# v0_9.net
KiCad netlist of a schematic drawn in EAGLE
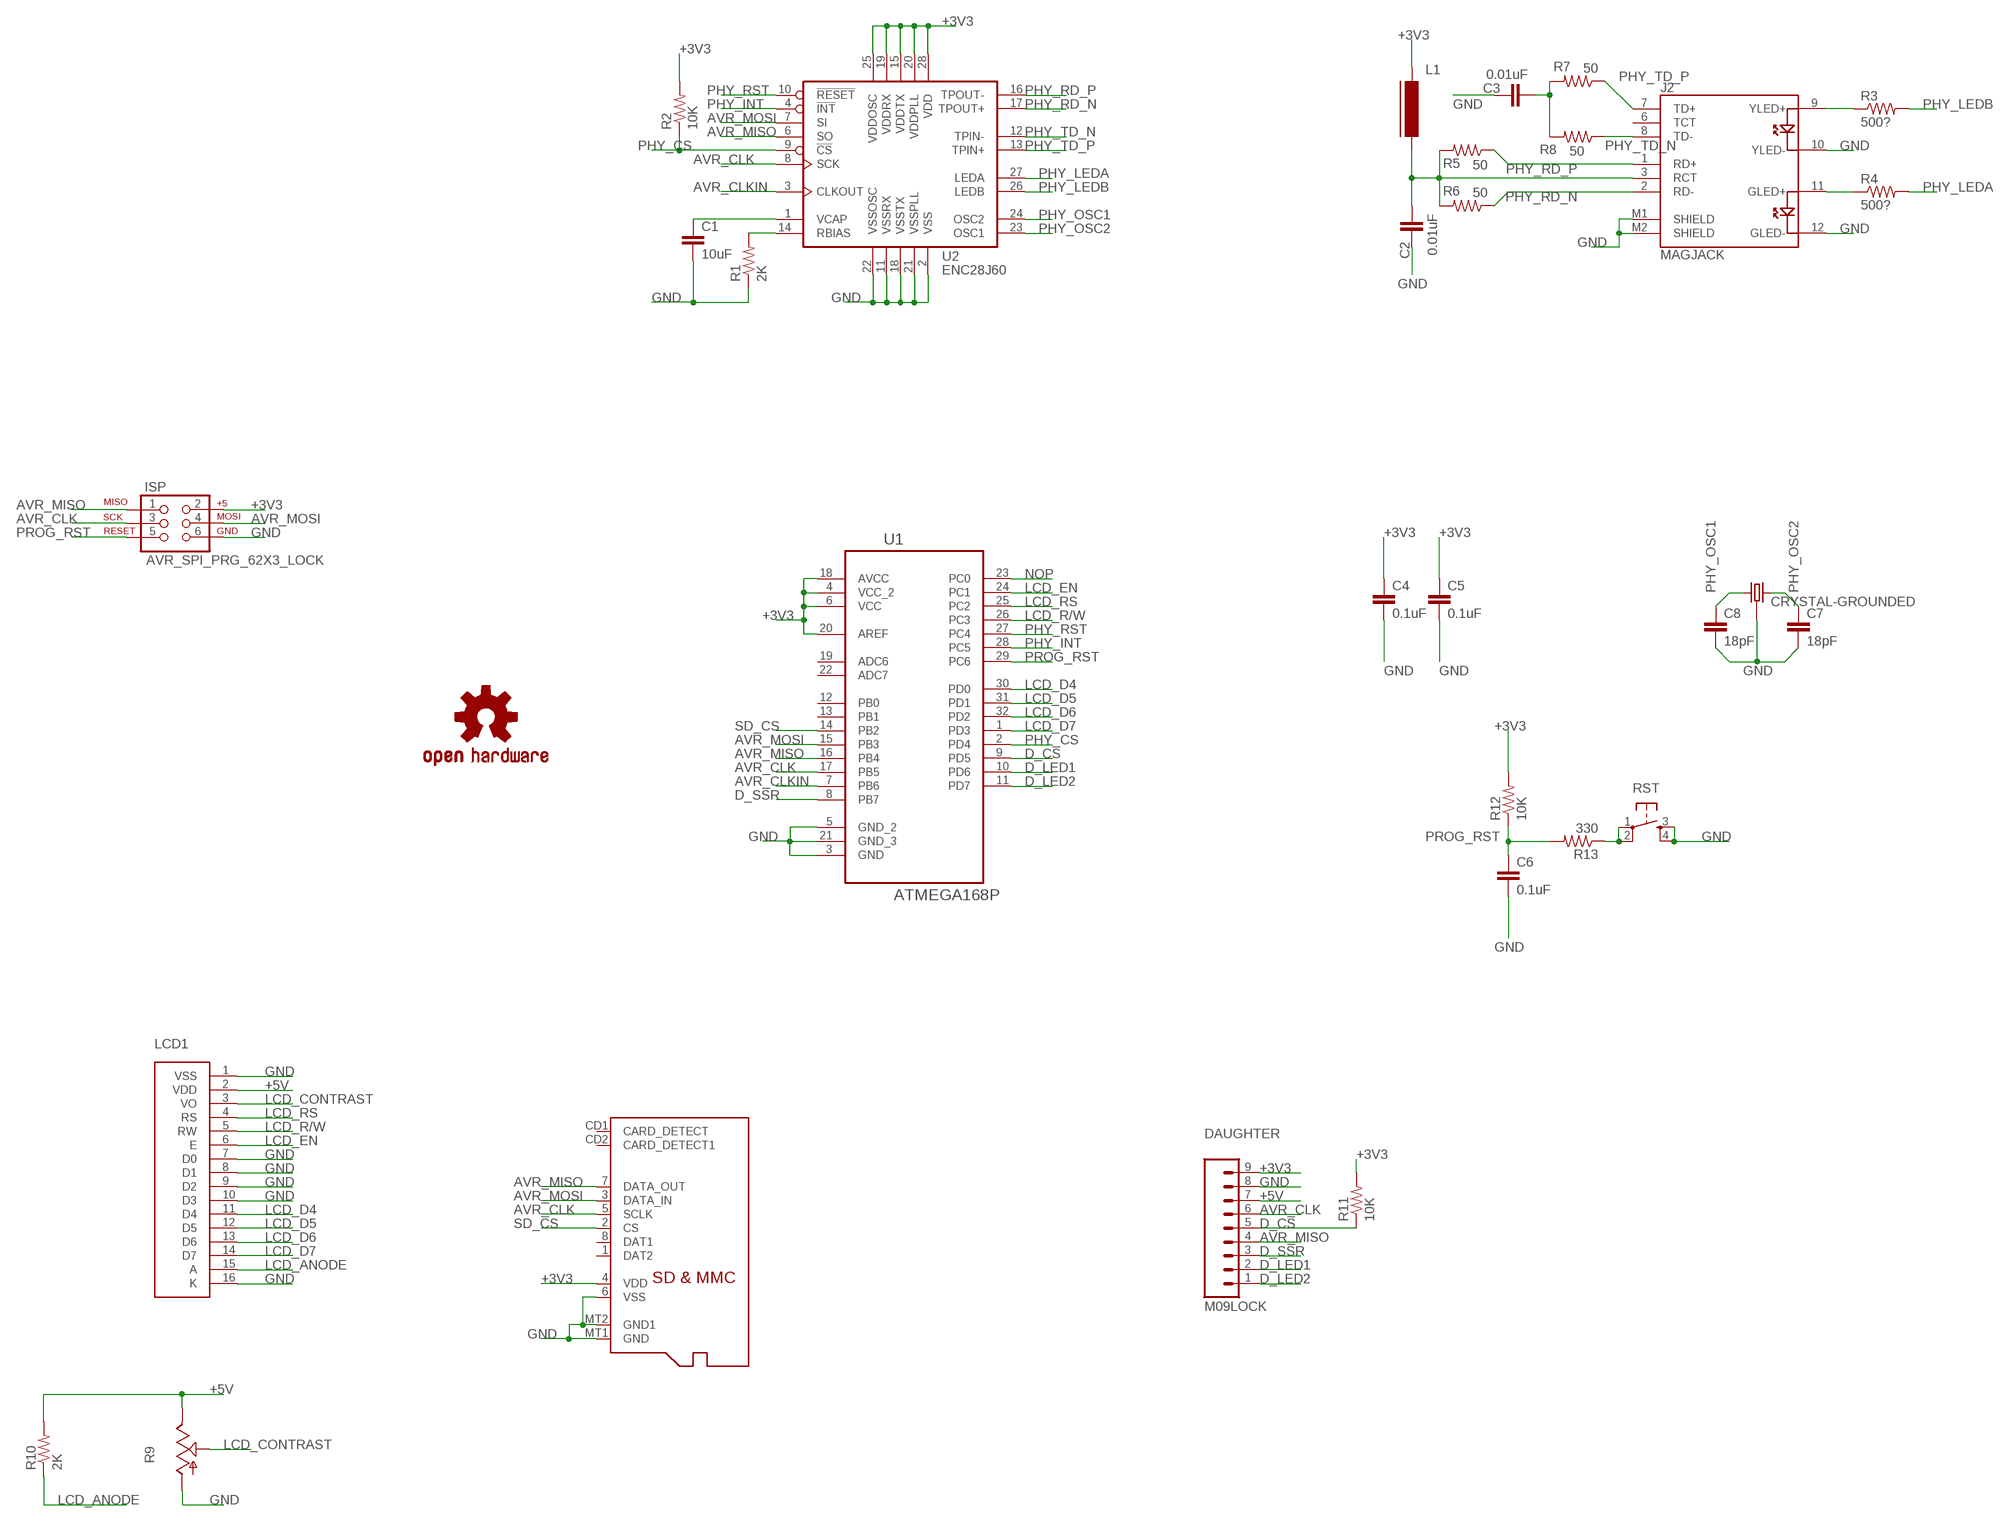
[diagram p0: schematic, sheet 1]

(export (version "E")
  (design (tool "Eeschema 10.0.6"))
  (components
    (comp (ref "C1")
      (value "10uF")
      (footprint "eagle-import:0603-CAP")
      (libsource (lib "eagle-import") (part "10UF-6.3V-20%(0603)"))
    )
    (comp (ref "C2")
      (value "0.01uF")
      (footprint "eagle-import:0603-CAP")
      (libsource (lib "eagle-import") (part "CAP0603-CAP"))
    )
    (comp (ref "C3")
      (value "0.01uF")
      (footprint "eagle-import:0603-CAP")
      (libsource (lib "eagle-import") (part "CAP0603-CAP"))
    )
    (comp (ref "C4")
      (value "0.1uF")
      (footprint "eagle-import:0402-CAP")
      (libsource (lib "eagle-import") (part "CAP0402-CAP"))
    )
    (comp (ref "C5")
      (value "0.1uF")
      (footprint "eagle-import:0402-CAP")
      (libsource (lib "eagle-import") (part "CAP0402-CAP"))
    )
    (comp (ref "C6")
      (value "0.1uF")
      (footprint "eagle-import:0603-CAP")
      (libsource (lib "eagle-import") (part "CAP0603-CAP"))
    )
    (comp (ref "C7")
      (value "18pF")
      (footprint "eagle-import:0402-CAP")
      (libsource (lib "eagle-import") (part "CAP0402-CAP"))
    )
    (comp (ref "C8")
      (value "18pF")
      (footprint "eagle-import:0402-CAP")
      (libsource (lib "eagle-import") (part "CAP0402-CAP"))
    )
    (comp (ref "DAUGHTER")
      (value "M09LOCK")
      (footprint "eagle-import:1X09_LOCK")
      (libsource (lib "eagle-import") (part "M09LOCK"))
    )
    (comp (ref "ISP")
      (value "AVR_SPI_PRG_62X3_LOCK")
      (footprint "eagle-import:2X3_LOCK")
      (libsource (lib "eagle-import") (part "AVR_SPI_PRG_62X3_LOCK"))
    )
    (comp (ref "J2")
      (value "MAGJACK")
      (footprint "eagle-import:MAGJACK")
      (libsource (lib "eagle-import") (part "MAGJACK"))
    )
    (comp (ref "L1")
      (value "FERRITE-0603")
      (footprint "eagle-import:FB603")
      (libsource (lib "eagle-import") (part "FERRITE-0603"))
    )
    (comp (ref "LCD1")
      (value "HD44780")
      (footprint "eagle-import:.1_16PIN")
      (libsource (lib "eagle-import") (part "HD44780"))
    )
    (comp (ref "LOGO1")
      (value "OSHW-LOGOS")
      (footprint "eagle-import:OSHW-LOGO-S")
      (libsource (lib "eagle-import") (part "OSHW-LOGOS"))
    )
    (comp (ref "R1")
      (value "2K")
      (footprint "eagle-import:0603-RES")
      (libsource (lib "eagle-import") (part "RESISTOR0603-RES"))
    )
    (comp (ref "R2")
      (value "10K")
      (footprint "eagle-import:0603-RES")
      (libsource (lib "eagle-import") (part "RESISTOR0603-RES"))
    )
    (comp (ref "R3")
      (value "500?")
      (footprint "eagle-import:0603-RES")
      (libsource (lib "eagle-import") (part "RESISTOR0603-RES"))
    )
    (comp (ref "R4")
      (value "500?")
      (footprint "eagle-import:0603-RES")
      (libsource (lib "eagle-import") (part "RESISTOR0603-RES"))
    )
    (comp (ref "R5")
      (value "50")
      (footprint "eagle-import:0603-RES")
      (libsource (lib "eagle-import") (part "RESISTOR0603-RES"))
    )
    (comp (ref "R6")
      (value "50")
      (footprint "eagle-import:0603-RES")
      (libsource (lib "eagle-import") (part "RESISTOR0603-RES"))
    )
    (comp (ref "R7")
      (value "50")
      (footprint "eagle-import:0603-RES")
      (libsource (lib "eagle-import") (part "RESISTOR0603-RES"))
    )
    (comp (ref "R8")
      (value "50")
      (footprint "eagle-import:0603-RES")
      (libsource (lib "eagle-import") (part "RESISTOR0603-RES"))
    )
    (comp (ref "R9")
      (value "TRIM_US-B64Y")
      (footprint "eagle-import:B64Y")
      (libsource (lib "eagle-import") (part "TRIM_US-B64Y"))
    )
    (comp (ref "R10")
      (value "2K")
      (footprint "eagle-import:0603-RES")
      (libsource (lib "eagle-import") (part "RESISTOR0603-RES"))
    )
    (comp (ref "R11")
      (value "10K")
      (footprint "eagle-import:0603-RES")
      (libsource (lib "eagle-import") (part "RESISTOR0603-RES"))
    )
    (comp (ref "R12")
      (value "10K")
      (footprint "eagle-import:0603-RES")
      (libsource (lib "eagle-import") (part "RESISTOR0603-RES"))
    )
    (comp (ref "R13")
      (value "330")
      (footprint "eagle-import:0603-RES")
      (libsource (lib "eagle-import") (part "RESISTOR0603-RES"))
    )
    (comp (ref "RST")
      (value "TAC_SWITCHSMD")
      (footprint "eagle-import:TACTILE-SWITCH-SMD")
      (libsource (lib "eagle-import") (part "TAC_SWITCHSMD"))
    )
    (comp (ref "SD")
      (value "MICROSD")
      (footprint "eagle-import:MICROSD")
      (libsource (lib "eagle-import") (part "MICROSD"))
    )
    (comp (ref "U1")
      (value "ATMEGA168P")
      (footprint "eagle-import:QFP80P900X900X120-32N")
      (fields (field (name "MPN") "ATMEGA168P-20AU"))
      (libsource (lib "eagle-import") (part "ATMEGA168P-20AU"))
    )
    (comp (ref "U2")
      (value "ENC28J60")
      (footprint "eagle-import:SOIC-28W")
      (libsource (lib "eagle-import") (part "IC_ENC28J60-SOIC-28"))
    )
    (comp (ref "Y1")
      (value "CRYSTAL-GROUNDED")
      (footprint "eagle-import:CRYSTAL-SMD-5X3")
      (libsource (lib "eagle-import") (part "CRYSTAL-GROUNDED"))
    )
  )
  (nets
    (net (code "1") (name "/+3V3") (class "Default")
      (node (ref "C4") (pin "1") (pinfunction "1_1") (pintype "passive"))
      (node (ref "C5") (pin "1") (pinfunction "1_1") (pintype "passive"))
      (node (ref "DAUGHTER") (pin "9") (pinfunction "9_9") (pintype "passive"))
      (node (ref "ISP") (pin "2") (pinfunction "2_2") (pintype "passive"))
      (node (ref "L1") (pin "1") (pinfunction "1_1") (pintype "passive"))
      (node (ref "R11") (pin "2") (pinfunction "2_2") (pintype "passive"))
      (node (ref "R12") (pin "2") (pinfunction "2_2") (pintype "passive"))
      (node (ref "R2") (pin "2") (pinfunction "2_2") (pintype "passive"))
      (node (ref "SD") (pin "4") (pinfunction "VDD_4") (pintype "power_in"))
      (node (ref "U1") (pin "18") (pinfunction "AVCC_18") (pintype "power_in"))
      (node (ref "U1") (pin "20") (pinfunction "AREF_20") (pintype "input"))
      (node (ref "U1") (pin "4") (pinfunction "VCC_2_4") (pintype "power_in"))
      (node (ref "U1") (pin "6") (pinfunction "VCC_6") (pintype "power_in"))
      (node (ref "U2") (pin "15") (pinfunction "VDDTX_15") (pintype "power_in"))
      (node (ref "U2") (pin "19") (pinfunction "VDDRX_19") (pintype "power_in"))
      (node (ref "U2") (pin "20") (pinfunction "VDDPLL_20") (pintype "power_in"))
      (node (ref "U2") (pin "25") (pinfunction "VDDOSC_25") (pintype "power_in"))
      (node (ref "U2") (pin "28") (pinfunction "VDD_28") (pintype "power_in"))
    )
    (net (code "2") (name "/+5V") (class "Default")
      (node (ref "DAUGHTER") (pin "7") (pinfunction "7_7") (pintype "passive"))
      (node (ref "LCD1") (pin "2") (pinfunction "VDD_2") (pintype "bidirectional"))
      (node (ref "R10") (pin "2") (pinfunction "2_2") (pintype "passive"))
      (node (ref "R9") (pin "E") (pinfunction "E_E") (pintype "passive"))
    )
    (net (code "3") (name "/AVR_CLK") (class "Default")
      (node (ref "DAUGHTER") (pin "6") (pinfunction "6_6") (pintype "passive"))
      (node (ref "ISP") (pin "3") (pinfunction "3_3") (pintype "passive"))
      (node (ref "SD") (pin "5") (pinfunction "SCLK_5") (pintype "input"))
      (node (ref "U1") (pin "17") (pinfunction "PB5_17") (pintype "bidirectional"))
      (node (ref "U2") (pin "8") (pinfunction "SCK_8") (pintype "input"))
    )
    (net (code "4") (name "/AVR_CLKIN") (class "Default")
      (node (ref "U1") (pin "7") (pinfunction "PB6_7") (pintype "bidirectional"))
      (node (ref "U2") (pin "3") (pinfunction "CLKOUT_3") (pintype "output"))
    )
    (net (code "5") (name "/AVR_MISO") (class "Default")
      (node (ref "DAUGHTER") (pin "4") (pinfunction "4_4") (pintype "passive"))
      (node (ref "ISP") (pin "1") (pinfunction "1_1") (pintype "passive"))
      (node (ref "SD") (pin "7") (pinfunction "DATA_OUT_7") (pintype "output"))
      (node (ref "U1") (pin "16") (pinfunction "PB4_16") (pintype "bidirectional"))
      (node (ref "U2") (pin "6") (pinfunction "SO_6") (pintype "output"))
    )
    (net (code "6") (name "/AVR_MOSI") (class "Default")
      (node (ref "ISP") (pin "4") (pinfunction "4_4") (pintype "passive"))
      (node (ref "SD") (pin "3") (pinfunction "DATA_IN_3") (pintype "input"))
      (node (ref "U1") (pin "15") (pinfunction "PB3_15") (pintype "bidirectional"))
      (node (ref "U2") (pin "7") (pinfunction "SI_7") (pintype "input"))
    )
    (net (code "7") (name "/D_CS") (class "Default")
      (node (ref "DAUGHTER") (pin "5") (pinfunction "5_5") (pintype "passive"))
      (node (ref "R11") (pin "1") (pinfunction "1_1") (pintype "passive"))
      (node (ref "U1") (pin "9") (pinfunction "PD5_9") (pintype "bidirectional"))
    )
    (net (code "8") (name "/D_LED1") (class "Default")
      (node (ref "DAUGHTER") (pin "2") (pinfunction "2_2") (pintype "passive"))
      (node (ref "U1") (pin "10") (pinfunction "PD6_10") (pintype "bidirectional"))
    )
    (net (code "9") (name "/D_LED2") (class "Default")
      (node (ref "DAUGHTER") (pin "1") (pinfunction "1_1") (pintype "passive"))
      (node (ref "U1") (pin "11") (pinfunction "PD7_11") (pintype "bidirectional"))
    )
    (net (code "10") (name "/D_SSR") (class "Default")
      (node (ref "DAUGHTER") (pin "3") (pinfunction "3_3") (pintype "passive"))
      (node (ref "U1") (pin "8") (pinfunction "PB7_8") (pintype "bidirectional"))
    )
    (net (code "11") (name "/GND") (class "Default")
      (node (ref "C1") (pin "2") (pinfunction "2_2") (pintype "passive"))
      (node (ref "C2") (pin "1") (pinfunction "1_1") (pintype "passive"))
      (node (ref "C3") (pin "1") (pinfunction "1_1") (pintype "passive"))
      (node (ref "C4") (pin "2") (pinfunction "2_2") (pintype "passive"))
      (node (ref "C5") (pin "2") (pinfunction "2_2") (pintype "passive"))
      (node (ref "C6") (pin "2") (pinfunction "2_2") (pintype "passive"))
      (node (ref "C7") (pin "2") (pinfunction "2_2") (pintype "passive"))
      (node (ref "C8") (pin "2") (pinfunction "2_2") (pintype "passive"))
      (node (ref "DAUGHTER") (pin "8") (pinfunction "8_8") (pintype "passive"))
      (node (ref "ISP") (pin "6") (pinfunction "6_6") (pintype "passive"))
      (node (ref "J2") (pin "10") (pinfunction "YLED-_10") (pintype "bidirectional"))
      (node (ref "J2") (pin "12") (pinfunction "GLED-_12") (pintype "bidirectional"))
      (node (ref "J2") (pin "M1") (pinfunction "SHIELD_M1") (pintype "bidirectional"))
      (node (ref "J2") (pin "M2") (pinfunction "SHIELD_M2") (pintype "bidirectional"))
      (node (ref "LCD1") (pin "1") (pinfunction "VSS_1") (pintype "bidirectional"))
      (node (ref "LCD1") (pin "10") (pinfunction "D3_10") (pintype "bidirectional"))
      (node (ref "LCD1") (pin "16") (pinfunction "K_16") (pintype "bidirectional"))
      (node (ref "LCD1") (pin "7") (pinfunction "D0_7") (pintype "bidirectional"))
      (node (ref "LCD1") (pin "8") (pinfunction "D1_8") (pintype "bidirectional"))
      (node (ref "LCD1") (pin "9") (pinfunction "D2_9") (pintype "bidirectional"))
      (node (ref "R1") (pin "1") (pinfunction "1_1") (pintype "passive"))
      (node (ref "R9") (pin "A") (pinfunction "A_A") (pintype "passive"))
      (node (ref "RST") (pin "3") (pinfunction "3_3") (pintype "passive"))
      (node (ref "RST") (pin "4") (pinfunction "4_4") (pintype "passive"))
      (node (ref "SD") (pin "6") (pinfunction "VSS_6") (pintype "power_in"))
      (node (ref "SD") (pin "MT1") (pinfunction "GND_MT1") (pintype "power_in"))
      (node (ref "SD") (pin "MT2") (pinfunction "GND1_MT2") (pintype "power_in"))
      (node (ref "U1") (pin "21") (pinfunction "GND_3_21") (pintype "passive"))
      (node (ref "U1") (pin "3") (pinfunction "GND_3") (pintype "passive"))
      (node (ref "U1") (pin "5") (pinfunction "GND_2_5") (pintype "passive"))
      (node (ref "U2") (pin "11") (pinfunction "VSSRX_11") (pintype "power_in"))
      (node (ref "U2") (pin "18") (pinfunction "VSSTX_18") (pintype "power_in"))
      (node (ref "U2") (pin "2") (pinfunction "VSS_2") (pintype "power_in"))
      (node (ref "U2") (pin "21") (pinfunction "VSSPLL_21") (pintype "power_in"))
      (node (ref "U2") (pin "22") (pinfunction "VSSOSC_22") (pintype "power_in"))
      (node (ref "Y1") (pin "2") (pinfunction "3_2") (pintype "passive"))
      (node (ref "Y1") (pin "4") (pinfunction "3_4") (pintype "passive"))
    )
    (net (code "12") (name "/LCD_ANODE") (class "Default")
      (node (ref "LCD1") (pin "15") (pinfunction "A_15") (pintype "bidirectional"))
      (node (ref "R10") (pin "1") (pinfunction "1_1") (pintype "passive"))
    )
    (net (code "13") (name "/LCD_CONTRAST") (class "Default")
      (node (ref "LCD1") (pin "3") (pinfunction "VO_3") (pintype "bidirectional"))
      (node (ref "R9") (pin "S") (pinfunction "S_S") (pintype "passive"))
    )
    (net (code "14") (name "/LCD_D4") (class "Default")
      (node (ref "LCD1") (pin "11") (pinfunction "D4_11") (pintype "bidirectional"))
      (node (ref "U1") (pin "30") (pinfunction "PD0_30") (pintype "bidirectional"))
    )
    (net (code "15") (name "/LCD_D5") (class "Default")
      (node (ref "LCD1") (pin "12") (pinfunction "D5_12") (pintype "bidirectional"))
      (node (ref "U1") (pin "31") (pinfunction "PD1_31") (pintype "bidirectional"))
    )
    (net (code "16") (name "/LCD_D6") (class "Default")
      (node (ref "LCD1") (pin "13") (pinfunction "D6_13") (pintype "bidirectional"))
      (node (ref "U1") (pin "32") (pinfunction "PD2_32") (pintype "bidirectional"))
    )
    (net (code "17") (name "/LCD_D7") (class "Default")
      (node (ref "LCD1") (pin "14") (pinfunction "D7_14") (pintype "bidirectional"))
      (node (ref "U1") (pin "1") (pinfunction "PD3_1") (pintype "bidirectional"))
    )
    (net (code "18") (name "/LCD_EN") (class "Default")
      (node (ref "LCD1") (pin "6") (pinfunction "E_6") (pintype "bidirectional"))
      (node (ref "U1") (pin "24") (pinfunction "PC1_24") (pintype "bidirectional"))
    )
    (net (code "19") (name "/LCD_RS") (class "Default")
      (node (ref "LCD1") (pin "4") (pinfunction "RS_4") (pintype "bidirectional"))
      (node (ref "U1") (pin "25") (pinfunction "PC2_25") (pintype "bidirectional"))
    )
    (net (code "20") (name "/LCD_R{slash}W") (class "Default")
      (node (ref "LCD1") (pin "5") (pinfunction "RW_5") (pintype "bidirectional"))
      (node (ref "U1") (pin "26") (pinfunction "PC3_26") (pintype "bidirectional"))
    )
    (net (code "21") (name "/NOP") (class "Default")
      (node (ref "U1") (pin "23") (pinfunction "PC0_23") (pintype "bidirectional"))
    )
    (net (code "22") (name "/PHY_CS") (class "Default")
      (node (ref "R2") (pin "1") (pinfunction "1_1") (pintype "passive"))
      (node (ref "U1") (pin "2") (pinfunction "PD4_2") (pintype "bidirectional"))
      (node (ref "U2") (pin "9") (pinfunction "~{CS}_9") (pintype "input"))
    )
    (net (code "23") (name "/PHY_INT") (class "Default")
      (node (ref "U1") (pin "28") (pinfunction "PC5_28") (pintype "bidirectional"))
      (node (ref "U2") (pin "4") (pinfunction "~{INT}_4") (pintype "output"))
    )
    (net (code "24") (name "/PHY_LEDA") (class "Default")
      (node (ref "R4") (pin "2") (pinfunction "2_2") (pintype "passive"))
      (node (ref "U2") (pin "27") (pinfunction "LEDA_27") (pintype "output"))
    )
    (net (code "25") (name "/PHY_LEDB") (class "Default")
      (node (ref "R3") (pin "2") (pinfunction "2_2") (pintype "passive"))
      (node (ref "U2") (pin "26") (pinfunction "LEDB_26") (pintype "output"))
    )
    (net (code "26") (name "/PHY_OSC1") (class "Default")
      (node (ref "C8") (pin "1") (pinfunction "1_1") (pintype "passive"))
      (node (ref "U2") (pin "24") (pinfunction "OSC2_24") (pintype "output"))
      (node (ref "Y1") (pin "3") (pinfunction "1_3") (pintype "passive"))
    )
    (net (code "27") (name "/PHY_OSC2") (class "Default")
      (node (ref "C7") (pin "1") (pinfunction "1_1") (pintype "passive"))
      (node (ref "U2") (pin "23") (pinfunction "OSC1_23") (pintype "input"))
      (node (ref "Y1") (pin "1") (pinfunction "2_1") (pintype "passive"))
    )
    (net (code "28") (name "/PHY_RD_N") (class "Default")
      (node (ref "J2") (pin "2") (pinfunction "RD-_2") (pintype "bidirectional"))
      (node (ref "R6") (pin "1") (pinfunction "1_1") (pintype "passive"))
      (node (ref "U2") (pin "17") (pinfunction "TPOUT+_17") (pintype "output"))
    )
    (net (code "29") (name "/PHY_RD_P") (class "Default")
      (node (ref "J2") (pin "1") (pinfunction "RD+_1") (pintype "bidirectional"))
      (node (ref "R5") (pin "1") (pinfunction "1_1") (pintype "passive"))
      (node (ref "U2") (pin "16") (pinfunction "TPOUT-_16") (pintype "output"))
    )
    (net (code "30") (name "/PHY_RST") (class "Default")
      (node (ref "U1") (pin "27") (pinfunction "PC4_27") (pintype "bidirectional"))
      (node (ref "U2") (pin "10") (pinfunction "~{RESET}_10") (pintype "input"))
    )
    (net (code "31") (name "/PHY_TD_N") (class "Default")
      (node (ref "J2") (pin "8") (pinfunction "TD-_8") (pintype "bidirectional"))
      (node (ref "R8") (pin "1") (pinfunction "1_1") (pintype "passive"))
      (node (ref "U2") (pin "12") (pinfunction "TPIN-_12") (pintype "input"))
    )
    (net (code "32") (name "/PHY_TD_P") (class "Default")
      (node (ref "J2") (pin "7") (pinfunction "TD+_7") (pintype "bidirectional"))
      (node (ref "R7") (pin "1") (pinfunction "1_1") (pintype "passive"))
      (node (ref "U2") (pin "13") (pinfunction "TPIN+_13") (pintype "input"))
    )
    (net (code "33") (name "/PROG_RST") (class "Default")
      (node (ref "C6") (pin "1") (pinfunction "1_1") (pintype "passive"))
      (node (ref "ISP") (pin "5") (pinfunction "5_5") (pintype "passive"))
      (node (ref "R12") (pin "1") (pinfunction "1_1") (pintype "passive"))
      (node (ref "R13") (pin "2") (pinfunction "2_2") (pintype "passive"))
      (node (ref "U1") (pin "29") (pinfunction "PC6_29") (pintype "bidirectional"))
    )
    (net (code "34") (name "/SD_CS") (class "Default")
      (node (ref "SD") (pin "2") (pinfunction "CS_2") (pintype "input"))
      (node (ref "U1") (pin "14") (pinfunction "PB2_14") (pintype "bidirectional"))
    )
    (net (code "35") (name "Net-(C3-Pad2)") (class "Default")
      (node (ref "C3") (pin "2") (pinfunction "2_2") (pintype "passive"))
      (node (ref "R7") (pin "2") (pinfunction "2_2") (pintype "passive"))
      (node (ref "R8") (pin "2") (pinfunction "2_2") (pintype "passive"))
    )
    (net (code "36") (name "Net-(J2-GLED+)") (class "Default")
      (node (ref "J2") (pin "11") (pinfunction "GLED+_11") (pintype "bidirectional"))
      (node (ref "R4") (pin "1") (pinfunction "1_1") (pintype "passive"))
    )
    (net (code "37") (name "Net-(J2-RCT)") (class "Default")
      (node (ref "C2") (pin "2") (pinfunction "2_2") (pintype "passive"))
      (node (ref "J2") (pin "3") (pinfunction "RCT_3") (pintype "bidirectional"))
      (node (ref "L1") (pin "2") (pinfunction "2_2") (pintype "passive"))
      (node (ref "R5") (pin "2") (pinfunction "2_2") (pintype "passive"))
      (node (ref "R6") (pin "2") (pinfunction "2_2") (pintype "passive"))
    )
    (net (code "38") (name "Net-(J2-YLED+)") (class "Default")
      (node (ref "J2") (pin "9") (pinfunction "YLED+_9") (pintype "bidirectional"))
      (node (ref "R3") (pin "1") (pinfunction "1_1") (pintype "passive"))
    )
    (net (code "39") (name "Net-(R13-Pad1)") (class "Default")
      (node (ref "R13") (pin "1") (pinfunction "1_1") (pintype "passive"))
      (node (ref "RST") (pin "1") (pinfunction "1_1") (pintype "passive"))
      (node (ref "RST") (pin "2") (pinfunction "2_2") (pintype "passive"))
    )
    (net (code "40") (name "Net-(U2-RBIAS)") (class "Default")
      (node (ref "R1") (pin "2") (pinfunction "2_2") (pintype "passive"))
      (node (ref "U2") (pin "14") (pinfunction "RBIAS_14") (pintype "input"))
    )
    (net (code "41") (name "Net-(U2-VCAP)") (class "Default")
      (node (ref "C1") (pin "1") (pinfunction "1_1") (pintype "passive"))
      (node (ref "U2") (pin "1") (pinfunction "VCAP_1") (pintype "input"))
    )
    (net (code "42") (name "unconnected-(J2-TCT-Pad6)") (class "Default")
      (node (ref "J2") (pin "6") (pinfunction "TCT_6") (pintype "bidirectional"))
    )
    (net (code "43") (name "unconnected-(SD-CARD_DETECT-PadCD1)") (class "Default")
      (node (ref "SD") (pin "CD1") (pinfunction "CARD_DETECT_CD1") (pintype "passive"))
    )
    (net (code "44") (name "unconnected-(SD-CARD_DETECT1-PadCD2)") (class "Default")
      (node (ref "SD") (pin "CD2") (pinfunction "CARD_DETECT1_CD2") (pintype "passive"))
    )
    (net (code "45") (name "unconnected-(SD-DAT1-Pad8)") (class "Default")
      (node (ref "SD") (pin "8") (pinfunction "DAT1_8") (pintype "bidirectional"))
    )
    (net (code "46") (name "unconnected-(SD-DAT2-Pad1)") (class "Default")
      (node (ref "SD") (pin "1") (pinfunction "DAT2_1") (pintype "bidirectional"))
    )
    (net (code "47") (name "unconnected-(U1-ADC6-Pad19)") (class "Default")
      (node (ref "U1") (pin "19") (pinfunction "ADC6_19") (pintype "input"))
    )
    (net (code "48") (name "unconnected-(U1-ADC7-Pad22)") (class "Default")
      (node (ref "U1") (pin "22") (pinfunction "ADC7_22") (pintype "input"))
    )
    (net (code "49") (name "unconnected-(U1-PB0-Pad12)") (class "Default")
      (node (ref "U1") (pin "12") (pinfunction "PB0_12") (pintype "bidirectional"))
    )
    (net (code "50") (name "unconnected-(U1-PB1-Pad13)") (class "Default")
      (node (ref "U1") (pin "13") (pinfunction "PB1_13") (pintype "bidirectional"))
    )
  )
)
